# MCP2551T.net
KiCad netlist of a schematic drawn in Altium Designer
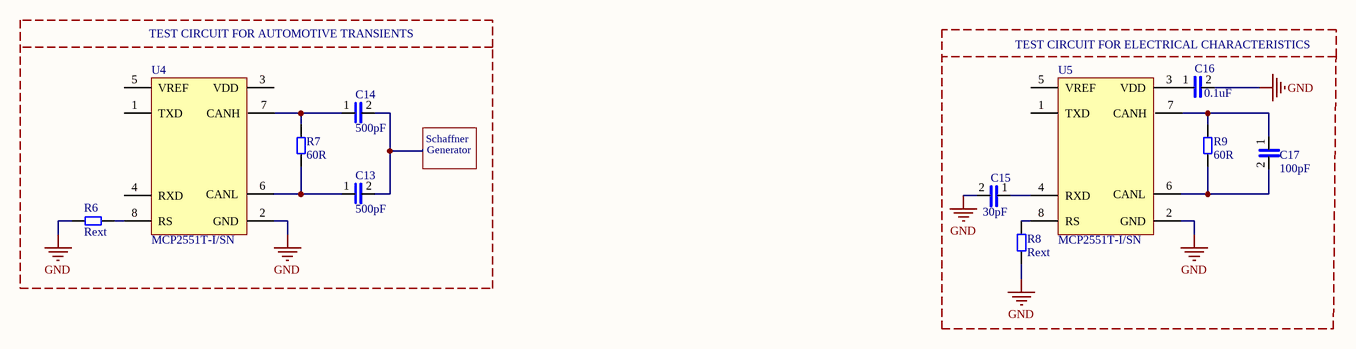
[diagram p0: MCP2551T.SchDoc]

(export (version "E")
  (design (tool "Eeschema 10.0.6"))
  (components
    (comp (ref "C13")
      (value "500pF")
      (footprint "CAP-0805-NP0")
      (description "CAP CER 3300PF 50V NPO 0805")
      (fields
        (field (name "MANUFACTURER") "Yageo")
        (field (name "MANUFACTURER PART NUMBER") "CC0805JKNPO9BN332")
      )
      (libsource (lib "") (part "CAP-0805-NP0-3.3nF_1"))
    )
    (comp (ref "C14")
      (value "500pF")
      (footprint "CAP-0805-NP0")
      (description "CAP CER 3300PF 50V NPO 0805")
      (fields
        (field (name "MANUFACTURER") "Yageo")
        (field (name "MANUFACTURER PART NUMBER") "CC0805JKNPO9BN332")
      )
      (libsource (lib "") (part "CAP-0805-NP0-3.3nF_1"))
    )
    (comp (ref "C15")
      (value "30pF")
      (footprint "CAP-0805-NP0")
      (description "CAP CER 3300PF 50V NPO 0805")
      (fields
        (field (name "MANUFACTURER") "Yageo")
        (field (name "MANUFACTURER PART NUMBER") "CC0805JKNPO9BN332")
      )
      (libsource (lib "Schlib1") (part "CAP-0805-NP0-3.3nF"))
    )
    (comp (ref "C16")
      (value "0.1uF")
      (footprint "CAP-0805-NP0")
      (description "CAP CER 3300PF 50V NPO 0805")
      (fields
        (field (name "MANUFACTURER") "Yageo")
        (field (name "MANUFACTURER PART NUMBER") "CC0805JKNPO9BN332")
      )
      (libsource (lib "") (part "CAP-0805-NP0-3.3nF_1"))
    )
    (comp (ref "C17")
      (value "100pF")
      (footprint "CAP-0805-NP0")
      (description "CAP CER 3300PF 50V NPO 0805")
      (fields
        (field (name "MANUFACTURER") "Yageo")
        (field (name "MANUFACTURER PART NUMBER") "CC0805JKNPO9BN332")
      )
      (libsource (lib "") (part "CAP-0805-NP0-3.3nF_2"))
    )
    (comp (ref "R6")
      (value "Rext")
      (footprint "RES-0805")
      (description "Res SMD 0805 10K 1% 0.125W T.C.100PPM")
      (fields
        (field (name "MANUFACTURER") "Yageo")
        (field (name "MANUFACTURER PART NUMBER") "RC0805FR-0710KL")
      )
      (libsource (lib "Schlib1") (part "RES-0805-10k"))
    )
    (comp (ref "R7")
      (value "60R")
      (footprint "RES-0805")
      (description "Res SMD 0805 10K 1% 0.125W T.C.100PPM")
      (fields
        (field (name "MANUFACTURER") "Yageo")
        (field (name "MANUFACTURER PART NUMBER") "RC0805FR-0710KL")
      )
      (libsource (lib "Schlib1") (part "RES-0805-10k"))
    )
    (comp (ref "R8")
      (value "Rext")
      (footprint "RES-0805")
      (description "Res SMD 0805 10K 1% 0.125W T.C.100PPM")
      (fields
        (field (name "MANUFACTURER") "Yageo")
        (field (name "MANUFACTURER PART NUMBER") "RC0805FR-0710KL")
      )
      (libsource (lib "Schlib1") (part "RES-0805-10k"))
    )
    (comp (ref "R9")
      (value "60R")
      (footprint "RES-0805")
      (description "Res SMD 0805 10K 1% 0.125W T.C.100PPM")
      (fields
        (field (name "MANUFACTURER") "Yageo")
        (field (name "MANUFACTURER PART NUMBER") "RC0805FR-0710KL")
      )
      (libsource (lib "Schlib1") (part "RES-0805-10k"))
    )
    (comp (ref "U4")
      (value "MCP2551T-I/SN")
      (footprint "MCP2551T")
      (description "1/1 Transceiver Half CAN 8-SOIC")
      (fields
        (field (name "MANUFACTURER") "Microchip")
        (field (name "MANUFACTURER PART NUMBER") "MCP2551-I/SN")
      )
      (libsource (lib "Schlib1") (part "MCP2551T-I/SN"))
    )
    (comp (ref "U5")
      (value "MCP2551T-I/SN")
      (footprint "MCP2551T")
      (description "1/1 Transceiver Half CAN 8-SOIC")
      (fields
        (field (name "MANUFACTURER") "Microchip")
        (field (name "MANUFACTURER PART NUMBER") "MCP2551-I/SN")
      )
      (libsource (lib "Schlib1") (part "MCP2551T-I/SN"))
    )
  )
  (nets
    (net (code "1") (name "GND") (class "Default")
      (node (ref "C15") (pin "2") (pinfunction "2_2") (pintype "passive"))
      (node (ref "C16") (pin "2") (pinfunction "2_2") (pintype "passive"))
      (node (ref "R6") (pin "1") (pinfunction "1_1") (pintype "passive"))
      (node (ref "R8") (pin "1") (pinfunction "1_1") (pintype "passive"))
      (node (ref "U4") (pin "2") (pinfunction "GND_2") (pintype "passive"))
      (node (ref "U5") (pin "2") (pinfunction "GND_2") (pintype "passive"))
    )
    (net (code "2") (name "Net-(C13-Pad2)") (class "Default")
      (node (ref "C13") (pin "2") (pinfunction "2_2") (pintype "passive"))
      (node (ref "C14") (pin "2") (pinfunction "2_2") (pintype "passive"))
    )
    (net (code "3") (name "Net-(U4-CANH)") (class "Default")
      (node (ref "C14") (pin "1") (pinfunction "1_1") (pintype "passive"))
      (node (ref "R7") (pin "2") (pinfunction "2_2") (pintype "passive"))
      (node (ref "U4") (pin "7") (pinfunction "CANH_7") (pintype "passive"))
    )
    (net (code "4") (name "Net-(U4-CANL)") (class "Default")
      (node (ref "C13") (pin "1") (pinfunction "1_1") (pintype "passive"))
      (node (ref "R7") (pin "1") (pinfunction "1_1") (pintype "passive"))
      (node (ref "U4") (pin "6") (pinfunction "CANL_6") (pintype "passive"))
    )
    (net (code "5") (name "Net-(U4-RS)") (class "Default")
      (node (ref "R6") (pin "2") (pinfunction "2_2") (pintype "passive"))
      (node (ref "U4") (pin "8") (pinfunction "RS_8") (pintype "passive"))
    )
    (net (code "6") (name "Net-(U5-CANH)") (class "Default")
      (node (ref "C17") (pin "1") (pinfunction "1_1") (pintype "passive"))
      (node (ref "R9") (pin "2") (pinfunction "2_2") (pintype "passive"))
      (node (ref "U5") (pin "7") (pinfunction "CANH_7") (pintype "passive"))
    )
    (net (code "7") (name "Net-(U5-CANL)") (class "Default")
      (node (ref "C17") (pin "2") (pinfunction "2_2") (pintype "passive"))
      (node (ref "R9") (pin "1") (pinfunction "1_1") (pintype "passive"))
      (node (ref "U5") (pin "6") (pinfunction "CANL_6") (pintype "passive"))
    )
    (net (code "8") (name "Net-(U5-RS)") (class "Default")
      (node (ref "R8") (pin "2") (pinfunction "2_2") (pintype "passive"))
      (node (ref "U5") (pin "8") (pinfunction "RS_8") (pintype "passive"))
    )
    (net (code "9") (name "Net-(U5-RXD)") (class "Default")
      (node (ref "C15") (pin "1") (pinfunction "1_1") (pintype "passive"))
      (node (ref "U5") (pin "4") (pinfunction "RXD_4") (pintype "passive"))
    )
    (net (code "10") (name "Net-(U5-VDD)") (class "Default")
      (node (ref "C16") (pin "1") (pinfunction "1_1") (pintype "passive"))
      (node (ref "U5") (pin "3") (pinfunction "VDD_3") (pintype "passive"))
    )
    (net (code "11") (name "unconnected-(U4-RXD-Pad4)") (class "Default")
      (node (ref "U4") (pin "4") (pinfunction "RXD_4") (pintype "passive"))
    )
    (net (code "12") (name "unconnected-(U4-TXD-Pad1)") (class "Default")
      (node (ref "U4") (pin "1") (pinfunction "TXD_1") (pintype "passive"))
    )
    (net (code "13") (name "unconnected-(U4-VDD-Pad3)") (class "Default")
      (node (ref "U4") (pin "3") (pinfunction "VDD_3") (pintype "passive"))
    )
    (net (code "14") (name "unconnected-(U4-VREF-Pad5)") (class "Default")
      (node (ref "U4") (pin "5") (pinfunction "VREF_5") (pintype "power_in"))
    )
    (net (code "15") (name "unconnected-(U5-TXD-Pad1)") (class "Default")
      (node (ref "U5") (pin "1") (pinfunction "TXD_1") (pintype "passive"))
    )
    (net (code "16") (name "unconnected-(U5-VREF-Pad5)") (class "Default")
      (node (ref "U5") (pin "5") (pinfunction "VREF_5") (pintype "power_in"))
    )
  )
)
